# ESP32_AC_Controller.net
KiCad netlist of a schematic drawn in Altium Designer
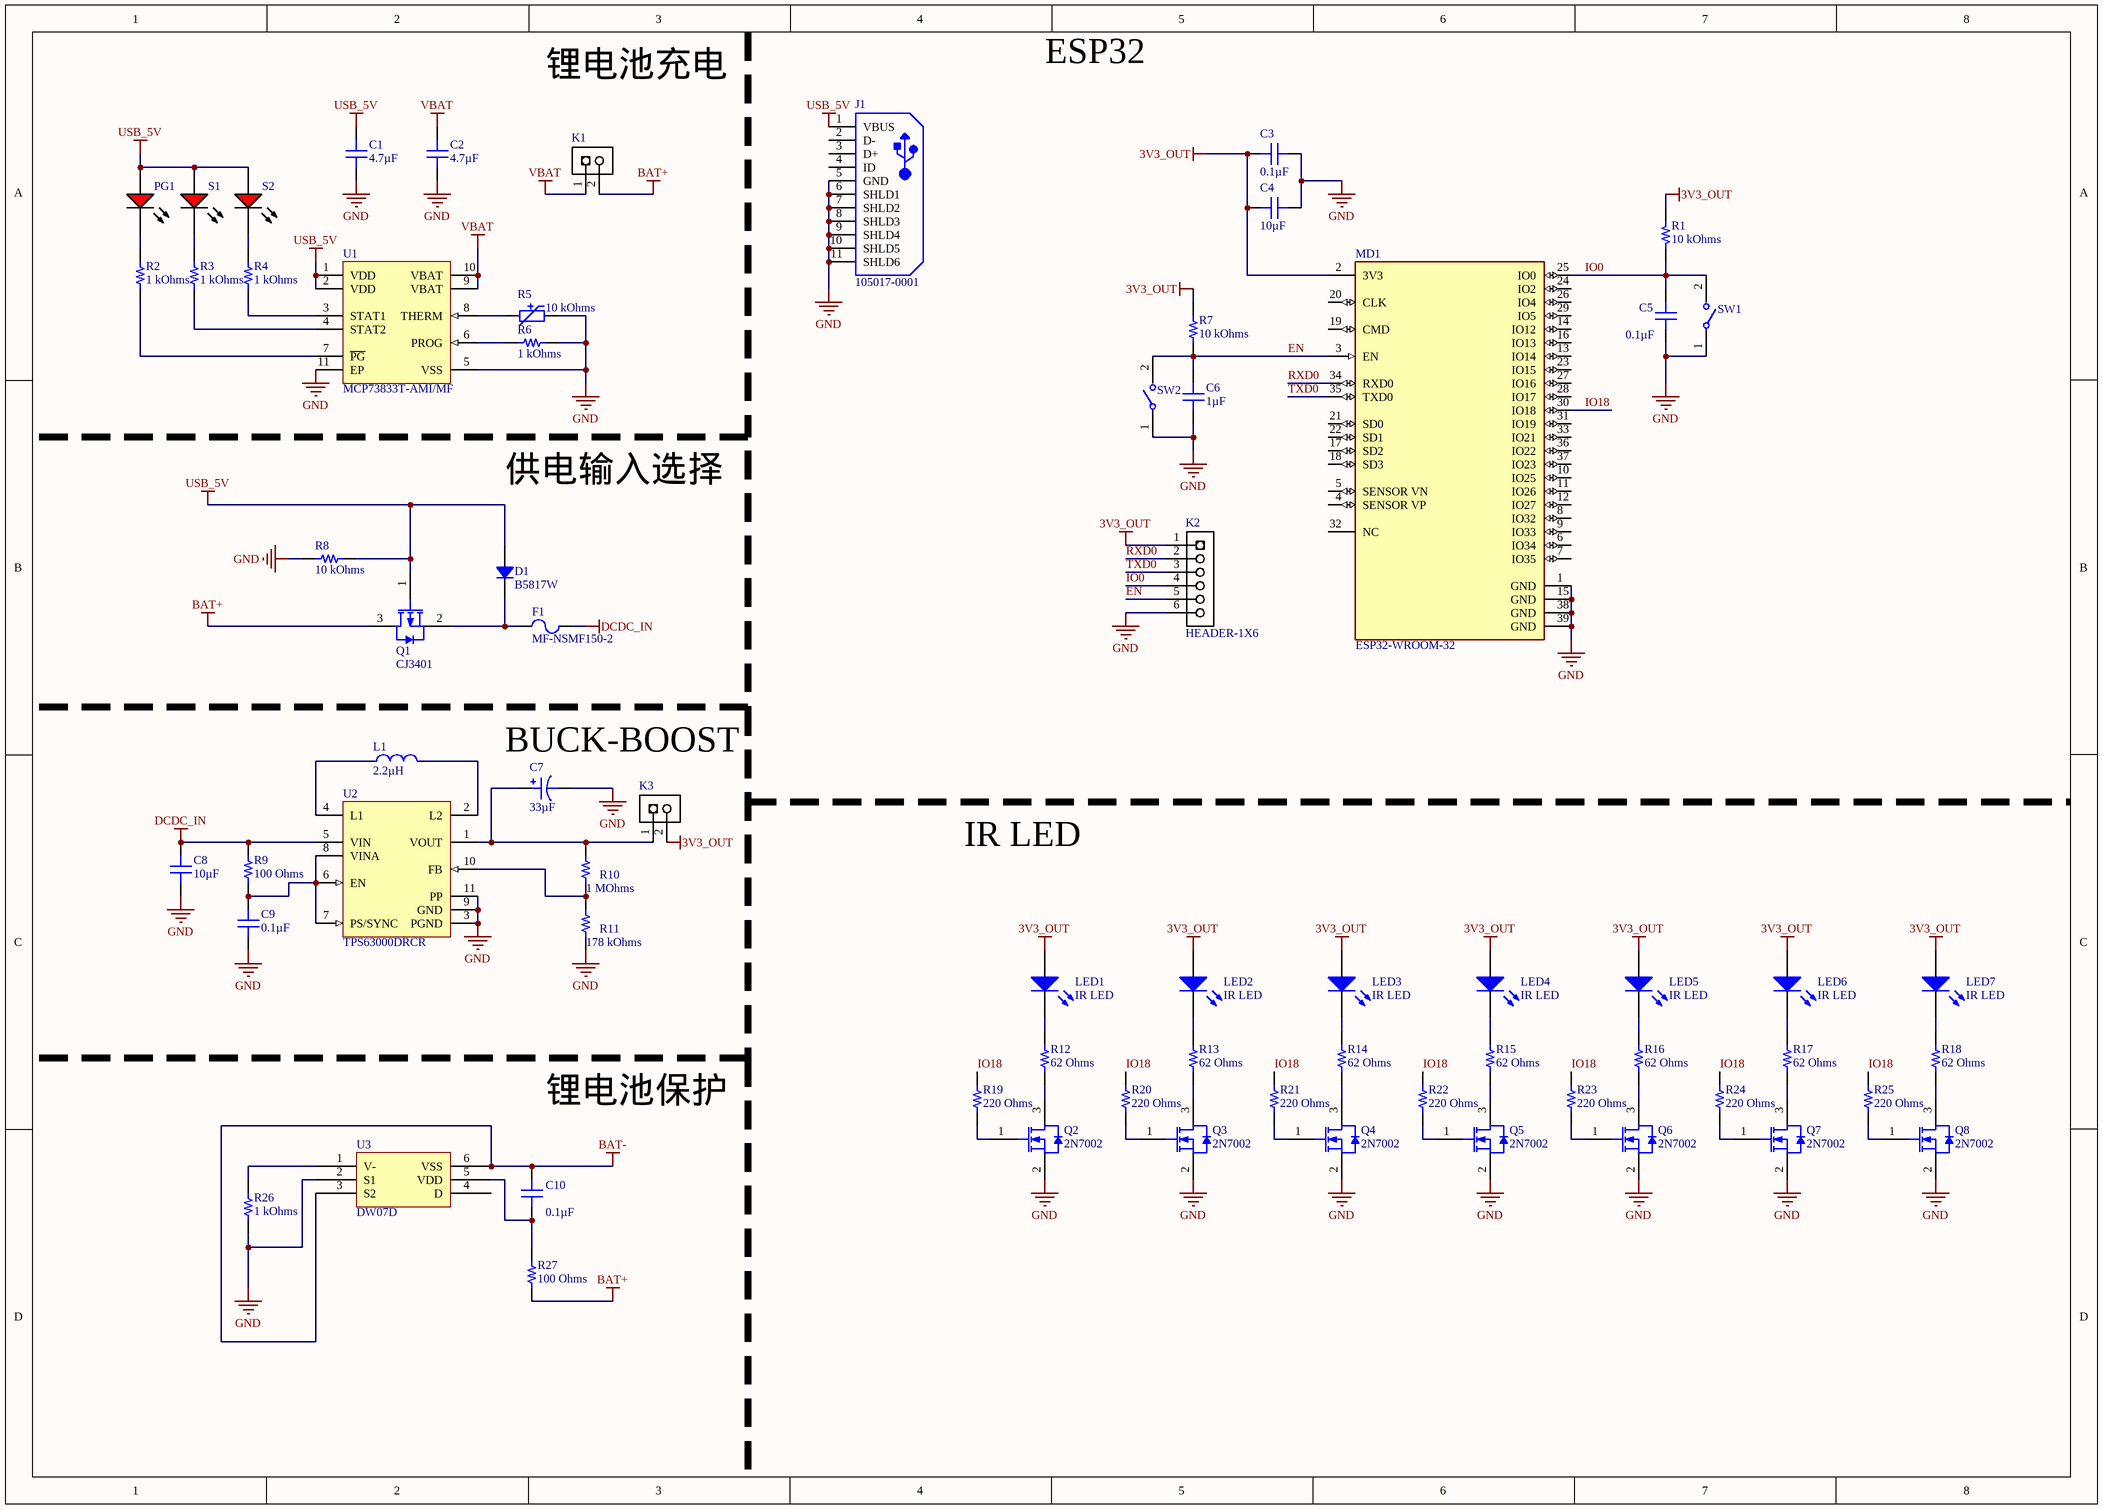
[diagram p0: ESP32_AC_Controller.SchDoc]

(export (version "E")
  (design (tool "Eeschema 10.0.6"))
  (components
    (comp (ref "C1")
      (value "4.7µF")
      (footprint "CAP 0603_1608")
      (description "CAP CER 0603 1UF 16V X7R 10%")
      (fields (field (name "PART NUMBER") "C0603C105K4RACAUTO") (field (name "MANUFACTURER") "KEMET"))
      (libsource (lib "Celestial Altium Library - altium_library") (part "Capacitor"))
    )
    (comp (ref "C2")
      (value "4.7µF")
      (footprint "CAP 0603_1608")
      (description "CAP CER 0603 1UF 16V X7R 10%")
      (fields (field (name "PART NUMBER") "C0603C105K4RACAUTO") (field (name "MANUFACTURER") "KEMET"))
      (libsource (lib "Celestial Altium Library - altium_library") (part "Capacitor"))
    )
    (comp (ref "C3")
      (value "0.1µF")
      (footprint "CAP 0603_1608")
      (description "CAP CER 0.1UF 10V X7R 0603")
      (fields (field (name "PART NUMBER") "C0603T104K8RAC7867") (field (name "MANUFACTURER") "KEMET"))
      (libsource (lib "Celestial Altium Library - altium_library") (part "Capacitor"))
    )
    (comp (ref "C4")
      (value "10µF")
      (footprint "CAP 0603_1608")
      (description "CAP CER 10UF 10V X5R 0603")
      (fields
        (field (name "PART NUMBER") "GRM188R61A106MAALD")
        (field (name "MANUFACTURER") "Murata Electronics")
      )
      (libsource (lib "Celestial Altium Library - altium_library") (part "Capacitor"))
    )
    (comp (ref "C5")
      (value "0.1µF")
      (footprint "CAP 0603_1608")
      (description "CAP CER 0.1UF 10V X7R 0603")
      (fields (field (name "PART NUMBER") "C0603T104K8RAC7867") (field (name "MANUFACTURER") "KEMET"))
      (libsource (lib "Celestial Altium Library - altium_library") (part "Capacitor"))
    )
    (comp (ref "C6")
      (value "1µF")
      (footprint "CAP 0603_1608")
      (description "CAP CER 1UF 10V X7R 0603")
      (fields (field (name "PART NUMBER") "CC0603KRX7R6BB105") (field (name "MANUFACTURER") "Yageo"))
      (libsource (lib "Celestial Altium Library - altium_library") (part "Capacitor"))
    )
    (comp (ref "C7")
      (value "33µF")
      (footprint "CAP POL 1411_3528")
      (description "CAP TANT 1UF 10% 35V 1411")
      (fields (field (name "PART NUMBER") "CWR11MH105KB") (field (name "MANUFACTURER") "KEMET"))
      (libsource (lib "Celestial Altium Library - altium_library") (part "Polarised Capacitor"))
    )
    (comp (ref "C8")
      (value "10µF")
      (footprint "CAP 0603_1608")
      (description "CAP CER 10UF 6.3V X5R 0603")
      (fields
        (field (name "PART NUMBER") "GRM188R60J106ME47D")
        (field (name "MANUFACTURER") "Murata Electronics")
      )
      (libsource (lib "Celestial Altium Library - altium_library") (part "Capacitor"))
    )
    (comp (ref "C9")
      (value "0.1µF")
      (footprint "CAP 0603_1608")
      (description "CAP CER 10UF 6.3V X5R 0603")
      (fields
        (field (name "PART NUMBER") "GRM188R60J106ME47D")
        (field (name "MANUFACTURER") "Murata Electronics")
      )
      (libsource (lib "Celestial Altium Library - altium_library") (part "Capacitor"))
    )
    (comp (ref "C10")
      (value "0.1µF")
      (footprint "CAP 0603_1608")
      (description "CAP CER 0.1UF 10V X7R 0603")
      (fields (field (name "PART NUMBER") "C0603T104K8RAC7867") (field (name "MANUFACTURER") "KEMET"))
      (libsource (lib "Celestial Altium Library - altium_library") (part "Capacitor"))
    )
    (comp (ref "D1")
      (value "B5817W")
      (footprint "SOD-123")
      (description "DIODE SCHOTTKY 30V 1A SOD-123")
      (fields (field (name "PART NUMBER") "B5818W-TP") (field (name "MANUFACTURER") "Micro Commercial Co"))
      (libsource (lib "Celestial Altium Library - altium_library") (part "Diode"))
    )
    (comp (ref "F1")
      (value "MF-NSMF150-2")
      (footprint "BOUR-MF-NSMF150-2_V")
      (description "PTC Resettable Fuse, 6 V, 100 A, -40 to 85 degC, 2-Pin SMD, RoHS, Tape and Reel")
      (fields (field (name "MANUFACTURER") "Bourns"))
      (libsource (lib "Altium Content Vault") (part "FUSE-2"))
    )
    (comp (ref "J1")
      (value "105017-0001")
      (footprint "USB-MICRO-B_V")
      (fields (field (name "MANUFACTURER") "Molex"))
      (libsource (lib "Altium Content Vault") (part "USB-5-6SHLD"))
    )
    (comp (ref "K1")
      (value "HEADER-1X2")
      (footprint "HEADER-1X2")
      (libsource (lib "vh_altium_library") (part "HEADER-1X2"))
    )
    (comp (ref "K2")
      (value "HEADER-1X6")
      (footprint "HEADER-1X6")
      (libsource (lib "vh_altium_library") (part "HEADER-1X6"))
    )
    (comp (ref "K3")
      (value "HEADER-1X2")
      (footprint "HEADER-1X2")
      (libsource (lib "vh_altium_library") (part "HEADER-1X2"))
    )
    (comp (ref "L1")
      (value "2.2µH")
      (footprint "FP-IHLP-2525CZ-FP_2_413x3-MFG")
      (description "Commercial Inductors, High Saturation Series 6.8uH 4.5A 60mΩ 20%")
      (fields (field (name "TOLERANCE") "20%"))
      (libsource (lib "Altium Content Vault") (part "725321dda6339637d4d059423bc1c3c"))
    )
    (comp (ref "LED1")
      (value "IR LED")
      (footprint "Type 5mm")
      (description "THT LED round mono-color waterclear, WL-TMRW ,Blue")
      (fields (field (name "MANUFACTURER") "Wuerth Elektronik") (field (name "PARTNUMBER") "151053BS04500"))
      (libsource (lib "Altium Content Vault") (part "WE-LED_K1A2-2"))
    )
    (comp (ref "LED2")
      (value "IR LED")
      (footprint "Type 5mm")
      (description "THT LED round mono-color waterclear, WL-TMRW ,Blue")
      (fields (field (name "MANUFACTURER") "Wuerth Elektronik") (field (name "PARTNUMBER") "151053BS04500"))
      (libsource (lib "Altium Content Vault") (part "WE-LED_K1A2-2"))
    )
    (comp (ref "LED3")
      (value "IR LED")
      (footprint "Type 5mm")
      (description "THT LED round mono-color waterclear, WL-TMRW ,Blue")
      (fields (field (name "MANUFACTURER") "Wuerth Elektronik") (field (name "PARTNUMBER") "151053BS04500"))
      (libsource (lib "Altium Content Vault") (part "WE-LED_K1A2-2"))
    )
    (comp (ref "LED4")
      (value "IR LED")
      (footprint "Type 5mm")
      (description "THT LED round mono-color waterclear, WL-TMRW ,Blue")
      (fields (field (name "MANUFACTURER") "Wuerth Elektronik") (field (name "PARTNUMBER") "151053BS04500"))
      (libsource (lib "Altium Content Vault") (part "WE-LED_K1A2-2"))
    )
    (comp (ref "LED5")
      (value "IR LED")
      (footprint "Type 5mm")
      (description "THT LED round mono-color waterclear, WL-TMRW ,Blue")
      (fields (field (name "MANUFACTURER") "Wuerth Elektronik") (field (name "PARTNUMBER") "151053BS04500"))
      (libsource (lib "Altium Content Vault") (part "WE-LED_K1A2-2"))
    )
    (comp (ref "LED6")
      (value "IR LED")
      (footprint "Type 5mm")
      (description "THT LED round mono-color waterclear, WL-TMRW ,Blue")
      (fields (field (name "MANUFACTURER") "Wuerth Elektronik") (field (name "PARTNUMBER") "151053BS04500"))
      (libsource (lib "Altium Content Vault") (part "WE-LED_K1A2-2"))
    )
    (comp (ref "LED7")
      (value "IR LED")
      (footprint "Type 5mm")
      (description "THT LED round mono-color waterclear, WL-TMRW ,Blue")
      (fields (field (name "MANUFACTURER") "Wuerth Elektronik") (field (name "PARTNUMBER") "151053BS04500"))
      (libsource (lib "Altium Content Vault") (part "WE-LED_K1A2-2"))
    )
    (comp (ref "MD1")
      (value "ESP32-WROOM-32")
      (footprint "FP-ESP32-WROOM-32-MFG")
      (description "RX TXRX MOD WIFI SURFACE MOUNT")
      (libsource (lib "Altium Content Vault") (part "ee866abf0b6c51247b7f5cdebf2f250"))
    )
    (comp (ref "PG1")
      (value "TLMS1100-GS08")
      (footprint "VISH-TLMX1100_V")
      (description "LED, RED, 2.1 V, -40 to 100 degC, 2-Pin SMD (0603), RoHS, Tape and Reel")
      (fields (field (name "TOLERANCE") "5%"))
      (libsource (lib "Altium Content Vault") (part "LED-RED-AK-2"))
    )
    (comp (ref "Q1")
      (value "CJ3401")
      (footprint "FAIR-SSOT3L-3_V")
      (fields (field (name "MANUFACTURER") "Fairchild Semiconductor"))
      (libsource (lib "Altium Content Vault") (part "PEMOS-GSD-3"))
    )
    (comp (ref "Q2")
      (value "2N7002")
      (footprint "STM-SOT-23-3_V")
      (description "N-channel 60 V, 1.8 Ohm, 0.35 A STripFET(TM) II Power MOSFET, SOT23")
      (fields (field (name "MANUFACTURER") "STMicroelectronics"))
      (libsource (lib "Altium Content Vault") (part "STM-NEMOS-G1S2D3-3"))
    )
    (comp (ref "Q3")
      (value "2N7002")
      (footprint "STM-SOT-23-3_V")
      (description "N-channel 60 V, 1.8 Ohm, 0.35 A STripFET(TM) II Power MOSFET, SOT23")
      (fields (field (name "MANUFACTURER") "STMicroelectronics"))
      (libsource (lib "Altium Content Vault") (part "STM-NEMOS-G1S2D3-3"))
    )
    (comp (ref "Q4")
      (value "2N7002")
      (footprint "STM-SOT-23-3_V")
      (description "N-channel 60 V, 1.8 Ohm, 0.35 A STripFET(TM) II Power MOSFET, SOT23")
      (fields (field (name "MANUFACTURER") "STMicroelectronics"))
      (libsource (lib "Altium Content Vault") (part "STM-NEMOS-G1S2D3-3"))
    )
    (comp (ref "Q5")
      (value "2N7002")
      (footprint "STM-SOT-23-3_V")
      (description "N-channel 60 V, 1.8 Ohm, 0.35 A STripFET(TM) II Power MOSFET, SOT23")
      (fields (field (name "MANUFACTURER") "STMicroelectronics"))
      (libsource (lib "Altium Content Vault") (part "STM-NEMOS-G1S2D3-3"))
    )
    (comp (ref "Q6")
      (value "2N7002")
      (footprint "STM-SOT-23-3_V")
      (description "N-channel 60 V, 1.8 Ohm, 0.35 A STripFET(TM) II Power MOSFET, SOT23")
      (fields (field (name "MANUFACTURER") "STMicroelectronics"))
      (libsource (lib "Altium Content Vault") (part "STM-NEMOS-G1S2D3-3"))
    )
    (comp (ref "Q7")
      (value "2N7002")
      (footprint "STM-SOT-23-3_V")
      (description "N-channel 60 V, 1.8 Ohm, 0.35 A STripFET(TM) II Power MOSFET, SOT23")
      (fields (field (name "MANUFACTURER") "STMicroelectronics"))
      (libsource (lib "Altium Content Vault") (part "STM-NEMOS-G1S2D3-3"))
    )
    (comp (ref "Q8")
      (value "2N7002")
      (footprint "STM-SOT-23-3_V")
      (description "N-channel 60 V, 1.8 Ohm, 0.35 A STripFET(TM) II Power MOSFET, SOT23")
      (fields (field (name "MANUFACTURER") "STMicroelectronics"))
      (libsource (lib "Altium Content Vault") (part "STM-NEMOS-G1S2D3-3"))
    )
    (comp (ref "R1")
      (value "10 kOhms")
      (footprint "RES 0603_1608")
      (description "RES 10K OHM 0.1% 1/16W 0603")
      (fields
        (field (name "PART NUMBER") "RNCS0603BKE10K0")
        (field (name "MANUFACTURER") "Stackpole Electronics Inc")
      )
      (libsource (lib "Celestial Altium Library - altium_library") (part "Resistor"))
    )
    (comp (ref "R2")
      (value "1 kOhms")
      (footprint "RES 0603_1608")
      (description "RES 10K OHM 0.1% 1/16W 0603")
      (fields
        (field (name "PART NUMBER") "RNCS0603BKE10K0")
        (field (name "MANUFACTURER") "Stackpole Electronics Inc")
      )
      (libsource (lib "Celestial Altium Library - altium_library") (part "Resistor"))
    )
    (comp (ref "R3")
      (value "1 kOhms")
      (footprint "RES 0603_1608")
      (description "RES 10K OHM 0.1% 1/16W 0603")
      (fields
        (field (name "PART NUMBER") "RNCS0603BKE10K0")
        (field (name "MANUFACTURER") "Stackpole Electronics Inc")
      )
      (libsource (lib "Celestial Altium Library - altium_library") (part "Resistor"))
    )
    (comp (ref "R4")
      (value "1 kOhms")
      (footprint "RES 0603_1608")
      (description "RES 10K OHM 0.1% 1/16W 0603")
      (fields
        (field (name "PART NUMBER") "RNCS0603BKE10K0")
        (field (name "MANUFACTURER") "Stackpole Electronics Inc")
      )
      (libsource (lib "Celestial Altium Library - altium_library") (part "Resistor"))
    )
    (comp (ref "R5")
      (value "10 kOhms")
      (footprint "PTC 0603_1608")
      (description "THERMISTOR PTC 470 OHM 50% 0603")
      (fields
        (field (name "PART NUMBER") "B59641A0145A062")
        (field (name "MANUFACTURER") "TDK Electronics Inc.")
      )
      (libsource (lib "Celestial Altium Library - altium_library") (part "Thermistor PTC"))
    )
    (comp (ref "R6")
      (value "1 kOhms")
      (footprint "RES 0603_1608")
      (description "RES 10K OHM 0.1% 1/16W 0603")
      (fields
        (field (name "PART NUMBER") "RNCS0603BKE10K0")
        (field (name "MANUFACTURER") "Stackpole Electronics Inc")
      )
      (libsource (lib "Celestial Altium Library - altium_library") (part "Resistor"))
    )
    (comp (ref "R7")
      (value "10 kOhms")
      (footprint "RES 0603_1608")
      (description "RES 10K OHM 0.1% 1/16W 0603")
      (fields
        (field (name "PART NUMBER") "RNCS0603BKE10K0")
        (field (name "MANUFACTURER") "Stackpole Electronics Inc")
      )
      (libsource (lib "Celestial Altium Library - altium_library") (part "Resistor"))
    )
    (comp (ref "R8")
      (value "10 kOhms")
      (footprint "RES 0603_1608")
      (description "RES 10K OHM 0.1% 1/16W 0603")
      (fields
        (field (name "PART NUMBER") "RNCS0603BKE10K0")
        (field (name "MANUFACTURER") "Stackpole Electronics Inc")
      )
      (libsource (lib "Celestial Altium Library - altium_library") (part "Resistor"))
    )
    (comp (ref "R9")
      (value "100 Ohms")
      (footprint "RES 0603_1608")
      (description "RES 10K OHM 0.1% 1/16W 0603")
      (fields
        (field (name "PART NUMBER") "RNCS0603BKE10K0")
        (field (name "MANUFACTURER") "Stackpole Electronics Inc")
      )
      (libsource (lib "Celestial Altium Library - altium_library") (part "Resistor"))
    )
    (comp (ref "R10")
      (value "1 MOhms")
      (footprint "RES 0603_1608")
      (description "RES 10K OHM 0.1% 1/16W 0603")
      (fields
        (field (name "PART NUMBER") "RNCS0603BKE10K0")
        (field (name "MANUFACTURER") "Stackpole Electronics Inc")
      )
      (libsource (lib "Celestial Altium Library - altium_library") (part "Resistor"))
    )
    (comp (ref "R11")
      (value "178 kOhms")
      (footprint "RES 0603_1608")
      (description "RES 10K OHM 0.1% 1/16W 0603")
      (fields
        (field (name "PART NUMBER") "RNCS0603BKE10K0")
        (field (name "MANUFACTURER") "Stackpole Electronics Inc")
      )
      (libsource (lib "Celestial Altium Library - altium_library") (part "Resistor"))
    )
    (comp (ref "R12")
      (value "62 Ohms")
      (footprint "RES 0603_1608")
      (description "RES SMD 62 OHM 1% 0.3W 0603")
      (fields (field (name "PART NUMBER") "SDR03EZPF62R0") (field (name "MANUFACTURER") "Rohm Semiconductor"))
      (libsource (lib "Celestial Altium Library - altium_library") (part "Resistor"))
    )
    (comp (ref "R13")
      (value "62 Ohms")
      (footprint "RES 0603_1608")
      (description "RES SMD 62 OHM 1% 0.3W 0603")
      (fields (field (name "PART NUMBER") "SDR03EZPF62R0") (field (name "MANUFACTURER") "Rohm Semiconductor"))
      (libsource (lib "Celestial Altium Library - altium_library") (part "Resistor"))
    )
    (comp (ref "R14")
      (value "62 Ohms")
      (footprint "RES 0603_1608")
      (description "RES SMD 62 OHM 1% 0.3W 0603")
      (fields (field (name "PART NUMBER") "SDR03EZPF62R0") (field (name "MANUFACTURER") "Rohm Semiconductor"))
      (libsource (lib "Celestial Altium Library - altium_library") (part "Resistor"))
    )
    (comp (ref "R15")
      (value "62 Ohms")
      (footprint "RES 0603_1608")
      (description "RES SMD 62 OHM 1% 0.3W 0603")
      (fields (field (name "PART NUMBER") "SDR03EZPF62R0") (field (name "MANUFACTURER") "Rohm Semiconductor"))
      (libsource (lib "Celestial Altium Library - altium_library") (part "Resistor"))
    )
    (comp (ref "R16")
      (value "62 Ohms")
      (footprint "RES 0603_1608")
      (description "RES SMD 62 OHM 1% 0.3W 0603")
      (fields (field (name "PART NUMBER") "SDR03EZPF62R0") (field (name "MANUFACTURER") "Rohm Semiconductor"))
      (libsource (lib "Celestial Altium Library - altium_library") (part "Resistor"))
    )
    (comp (ref "R17")
      (value "62 Ohms")
      (footprint "RES 0603_1608")
      (description "RES SMD 62 OHM 1% 0.3W 0603")
      (fields (field (name "PART NUMBER") "SDR03EZPF62R0") (field (name "MANUFACTURER") "Rohm Semiconductor"))
      (libsource (lib "Celestial Altium Library - altium_library") (part "Resistor"))
    )
    (comp (ref "R18")
      (value "62 Ohms")
      (footprint "RES 0603_1608")
      (description "RES SMD 62 OHM 1% 0.3W 0603")
      (fields (field (name "PART NUMBER") "SDR03EZPF62R0") (field (name "MANUFACTURER") "Rohm Semiconductor"))
      (libsource (lib "Celestial Altium Library - altium_library") (part "Resistor"))
    )
    (comp (ref "R19")
      (value "220 Ohms")
      (footprint "RES 0603_1608")
      (description "RES SMD 220 OHM 0.1% 1/16W 0603")
      (fields
        (field (name "PART NUMBER") "CPF0603B220RE1")
        (field (name "MANUFACTURER") "TE Connectivity Passive Product")
      )
      (libsource (lib "Celestial Altium Library - altium_library") (part "Resistor"))
    )
    (comp (ref "R20")
      (value "220 Ohms")
      (footprint "RES 0603_1608")
      (description "RES SMD 220 OHM 0.1% 1/16W 0603")
      (fields
        (field (name "PART NUMBER") "CPF0603B220RE1")
        (field (name "MANUFACTURER") "TE Connectivity Passive Product")
      )
      (libsource (lib "Celestial Altium Library - altium_library") (part "Resistor"))
    )
    (comp (ref "R21")
      (value "220 Ohms")
      (footprint "RES 0603_1608")
      (description "RES SMD 220 OHM 0.1% 1/16W 0603")
      (fields
        (field (name "PART NUMBER") "CPF0603B220RE1")
        (field (name "MANUFACTURER") "TE Connectivity Passive Product")
      )
      (libsource (lib "Celestial Altium Library - altium_library") (part "Resistor"))
    )
    (comp (ref "R22")
      (value "220 Ohms")
      (footprint "RES 0603_1608")
      (description "RES SMD 220 OHM 0.1% 1/16W 0603")
      (fields
        (field (name "PART NUMBER") "CPF0603B220RE1")
        (field (name "MANUFACTURER") "TE Connectivity Passive Product")
      )
      (libsource (lib "Celestial Altium Library - altium_library") (part "Resistor"))
    )
    (comp (ref "R23")
      (value "220 Ohms")
      (footprint "RES 0603_1608")
      (description "RES SMD 220 OHM 0.1% 1/16W 0603")
      (fields
        (field (name "PART NUMBER") "CPF0603B220RE1")
        (field (name "MANUFACTURER") "TE Connectivity Passive Product")
      )
      (libsource (lib "Celestial Altium Library - altium_library") (part "Resistor"))
    )
    (comp (ref "R24")
      (value "220 Ohms")
      (footprint "RES 0603_1608")
      (description "RES SMD 220 OHM 0.1% 1/16W 0603")
      (fields
        (field (name "PART NUMBER") "CPF0603B220RE1")
        (field (name "MANUFACTURER") "TE Connectivity Passive Product")
      )
      (libsource (lib "Celestial Altium Library - altium_library") (part "Resistor"))
    )
    (comp (ref "R25")
      (value "220 Ohms")
      (footprint "RES 0603_1608")
      (description "RES SMD 220 OHM 0.1% 1/16W 0603")
      (fields
        (field (name "PART NUMBER") "CPF0603B220RE1")
        (field (name "MANUFACTURER") "TE Connectivity Passive Product")
      )
      (libsource (lib "Celestial Altium Library - altium_library") (part "Resistor"))
    )
    (comp (ref "R26")
      (value "1 kOhms")
      (footprint "RES 0603_1608")
      (description "RES SMD 1K OHM 1% 1/10W 0603")
      (fields (field (name "PART NUMBER") "AC0603FR-071KL") (field (name "MANUFACTURER") "Yageo"))
      (libsource (lib "Celestial Altium Library - altium_library") (part "Resistor"))
    )
    (comp (ref "R27")
      (value "100 Ohms")
      (footprint "RES 0603_1608")
      (description "RES SMD 100 OHM 1% 1/10W 0603")
      (fields (field (name "PART NUMBER") "AC0603FR-07100RL") (field (name "MANUFACTURER") "Yageo"))
      (libsource (lib "Celestial Altium Library - altium_library") (part "Resistor"))
    )
    (comp (ref "S1")
      (value "TLMS1100-GS08")
      (footprint "VISH-TLMX1100_V")
      (description "LED, RED, 2.1 V, -40 to 100 degC, 2-Pin SMD (0603), RoHS, Tape and Reel")
      (fields (field (name "TOLERANCE") "5%"))
      (libsource (lib "Altium Content Vault") (part "LED-RED-AK-2"))
    )
    (comp (ref "S2")
      (value "TLMS1100-GS08")
      (footprint "VISH-TLMX1100_V")
      (description "LED, RED, 2.1 V, -40 to 100 degC, 2-Pin SMD (0603), RoHS, Tape and Reel")
      (fields (field (name "TOLERANCE") "5%"))
      (libsource (lib "Altium Content Vault") (part "LED-RED-AK-2"))
    )
    (comp (ref "SW1")
      (value "B3U-1000P")
      (footprint "FP-B3U-1000P-MFG")
      (description "SWITCH TACTILE SPST-NO 0.05A 12V")
      (libsource (lib "Altium Content Vault") (part "ae622034201233ca1abcedc05908f33"))
    )
    (comp (ref "SW2")
      (value "B3U-1000P")
      (footprint "FP-B3U-1000P-MFG")
      (description "SWITCH TACTILE SPST-NO 0.05A 12V")
      (libsource (lib "Altium Content Vault") (part "ae622034201233ca1abcedc05908f33"))
    )
    (comp (ref "U1")
      (value "MCP73833T-AMI/MF")
      (footprint "DFN-MF10")
      (libsource (lib "Altium Content Vault") (part "PM-BM-MCP73833-IL11"))
    )
    (comp (ref "U2")
      (value "TPS63000DRCR")
      (footprint "DRC0010J_V")
      (fields (field (name "MANUFACTURER") "Texas Instruments"))
      (libsource (lib "Altium Content Vault") (part "TI-TPS63000DRC10-3000X1650TP"))
    )
    (comp (ref "U3")
      (value "DW07D")
      (footprint "DW07D")
      (description "锂电池保护IC")
      (libsource (lib "MyIntegrated_Library") (part "DW07D"))
    )
  )
  (nets
    (net (code "1") (name "/EN") (class "Default")
      (node (ref "C6") (pin "2") (pinfunction "2_2") (pintype "passive"))
      (node (ref "K2") (pin "5") (pintype "passive"))
      (node (ref "MD1") (pin "3") (pinfunction "EN_3") (pintype "input"))
      (node (ref "R7") (pin "1") (pinfunction "1_1") (pintype "passive"))
      (node (ref "SW2") (pin "2") (pinfunction "2_2") (pintype "passive"))
    )
    (net (code "2") (name "/IO0") (class "Default")
      (node (ref "C5") (pin "1") (pinfunction "1_1") (pintype "passive"))
      (node (ref "K2") (pin "4") (pintype "passive"))
      (node (ref "MD1") (pin "25") (pinfunction "IO0_25") (pintype "bidirectional"))
      (node (ref "R1") (pin "1") (pinfunction "1_1") (pintype "passive"))
      (node (ref "SW1") (pin "2") (pinfunction "2_2") (pintype "passive"))
    )
    (net (code "3") (name "/IO18") (class "Default")
      (node (ref "MD1") (pin "30") (pinfunction "IO18_30") (pintype "bidirectional"))
      (node (ref "R19") (pin "2") (pinfunction "2_2") (pintype "passive"))
      (node (ref "R20") (pin "2") (pinfunction "2_2") (pintype "passive"))
      (node (ref "R21") (pin "2") (pinfunction "2_2") (pintype "passive"))
      (node (ref "R22") (pin "2") (pinfunction "2_2") (pintype "passive"))
      (node (ref "R23") (pin "2") (pinfunction "2_2") (pintype "passive"))
      (node (ref "R24") (pin "2") (pinfunction "2_2") (pintype "passive"))
      (node (ref "R25") (pin "2") (pinfunction "2_2") (pintype "passive"))
    )
    (net (code "4") (name "/RXD0") (class "Default")
      (node (ref "K2") (pin "2") (pintype "passive"))
      (node (ref "MD1") (pin "34") (pinfunction "RXD0_34") (pintype "bidirectional"))
    )
    (net (code "5") (name "/TXD0") (class "Default")
      (node (ref "K2") (pin "3") (pintype "passive"))
      (node (ref "MD1") (pin "35") (pinfunction "TXD0_35") (pintype "bidirectional"))
    )
    (net (code "6") (name "3V3_OUT") (class "Default")
      (node (ref "C3") (pin "2") (pinfunction "2_2") (pintype "passive"))
      (node (ref "C4") (pin "1") (pinfunction "1_1") (pintype "passive"))
      (node (ref "K2") (pin "1") (pintype "passive"))
      (node (ref "K3") (pin "2") (pintype "passive"))
      (node (ref "LED1") (pin "2") (pinfunction "A_2") (pintype "passive"))
      (node (ref "LED2") (pin "2") (pinfunction "A_2") (pintype "passive"))
      (node (ref "LED3") (pin "2") (pinfunction "A_2") (pintype "passive"))
      (node (ref "LED4") (pin "2") (pinfunction "A_2") (pintype "passive"))
      (node (ref "LED5") (pin "2") (pinfunction "A_2") (pintype "passive"))
      (node (ref "LED6") (pin "2") (pinfunction "A_2") (pintype "passive"))
      (node (ref "LED7") (pin "2") (pinfunction "A_2") (pintype "passive"))
      (node (ref "MD1") (pin "2") (pinfunction "3V3_2") (pintype "power_in"))
      (node (ref "R1") (pin "2") (pinfunction "2_2") (pintype "passive"))
      (node (ref "R7") (pin "2") (pinfunction "2_2") (pintype "passive"))
    )
    (net (code "7") (name "BAT+") (class "Default")
      (node (ref "K1") (pin "2") (pintype "passive"))
      (node (ref "Q1") (pin "3") (pinfunction "DRAIN_3") (pintype "passive"))
      (node (ref "R27") (pin "1") (pinfunction "1_1") (pintype "passive"))
    )
    (net (code "8") (name "BAT-") (class "Default")
      (node (ref "C10") (pin "1") (pinfunction "1_1") (pintype "passive"))
      (node (ref "U3") (pin "3") (pinfunction "S2_3") (pintype "passive"))
      (node (ref "U3") (pin "6") (pinfunction "VSS_6") (pintype "passive"))
    )
    (net (code "9") (name "DCDC_IN") (class "Default")
      (node (ref "C8") (pin "2") (pinfunction "2_2") (pintype "passive"))
      (node (ref "F1") (pin "2") (pinfunction "2_2") (pintype "passive"))
      (node (ref "R9") (pin "1") (pinfunction "1_1") (pintype "passive"))
      (node (ref "U2") (pin "5") (pinfunction "VIN_5") (pintype "power_in"))
    )
    (net (code "10") (name "GND") (class "Default")
      (node (ref "C1") (pin "1") (pinfunction "1_1") (pintype "passive"))
      (node (ref "C2") (pin "1") (pinfunction "1_1") (pintype "passive"))
      (node (ref "C3") (pin "1") (pinfunction "1_1") (pintype "passive"))
      (node (ref "C4") (pin "2") (pinfunction "2_2") (pintype "passive"))
      (node (ref "C5") (pin "2") (pinfunction "2_2") (pintype "passive"))
      (node (ref "C6") (pin "1") (pinfunction "1_1") (pintype "passive"))
      (node (ref "C7") (pin "2") (pinfunction "2_2") (pintype "passive"))
      (node (ref "C8") (pin "1") (pinfunction "1_1") (pintype "passive"))
      (node (ref "C9") (pin "2") (pinfunction "2_2") (pintype "passive"))
      (node (ref "J1") (pin "10") (pinfunction "SHLD5_10") (pintype "passive"))
      (node (ref "J1") (pin "11") (pinfunction "SHLD6_11") (pintype "passive"))
      (node (ref "J1") (pin "5") (pinfunction "GND_5") (pintype "passive"))
      (node (ref "J1") (pin "6") (pinfunction "SHLD1_6") (pintype "passive"))
      (node (ref "J1") (pin "7") (pinfunction "SHLD2_7") (pintype "passive"))
      (node (ref "J1") (pin "8") (pinfunction "SHLD3_8") (pintype "passive"))
      (node (ref "J1") (pin "9") (pinfunction "SHLD4_9") (pintype "passive"))
      (node (ref "K2") (pin "6") (pintype "passive"))
      (node (ref "MD1") (pin "1") (pinfunction "GND_1") (pintype "power_in"))
      (node (ref "MD1") (pin "15") (pinfunction "GND_15") (pintype "power_in"))
      (node (ref "MD1") (pin "38") (pinfunction "GND_38") (pintype "power_in"))
      (node (ref "MD1") (pin "39") (pinfunction "GND_39") (pintype "power_in"))
      (node (ref "Q2") (pin "2") (pinfunction "S_2") (pintype "passive"))
      (node (ref "Q3") (pin "2") (pinfunction "S_2") (pintype "passive"))
      (node (ref "Q4") (pin "2") (pinfunction "S_2") (pintype "passive"))
      (node (ref "Q5") (pin "2") (pinfunction "S_2") (pintype "passive"))
      (node (ref "Q6") (pin "2") (pinfunction "S_2") (pintype "passive"))
      (node (ref "Q7") (pin "2") (pinfunction "S_2") (pintype "passive"))
      (node (ref "Q8") (pin "2") (pinfunction "S_2") (pintype "passive"))
      (node (ref "R11") (pin "2") (pinfunction "2_2") (pintype "passive"))
      (node (ref "R26") (pin "1") (pinfunction "1_1") (pintype "passive"))
      (node (ref "R5") (pin "1") (pinfunction "1_1") (pintype "passive"))
      (node (ref "R6") (pin "1") (pinfunction "1_1") (pintype "passive"))
      (node (ref "R8") (pin "2") (pinfunction "2_2") (pintype "passive"))
      (node (ref "SW1") (pin "1") (pinfunction "1_1") (pintype "passive"))
      (node (ref "SW2") (pin "1") (pinfunction "1_1") (pintype "passive"))
      (node (ref "U1") (pin "11") (pinfunction "EP_11") (pintype "power_in"))
      (node (ref "U1") (pin "5") (pinfunction "VSS_5") (pintype "power_in"))
      (node (ref "U2") (pin "11") (pinfunction "PP_11") (pintype "power_in"))
      (node (ref "U2") (pin "3") (pinfunction "PGND_3") (pintype "power_in"))
      (node (ref "U2") (pin "9") (pinfunction "GND_9") (pintype "power_in"))
      (node (ref "U3") (pin "2") (pinfunction "S1_2") (pintype "passive"))
    )
    (net (code "11") (name "Net-(LED1-K)") (class "Default")
      (node (ref "LED1") (pin "1") (pinfunction "K_1") (pintype "passive"))
      (node (ref "R12") (pin "2") (pinfunction "2_2") (pintype "passive"))
    )
    (net (code "12") (name "Net-(LED2-K)") (class "Default")
      (node (ref "LED2") (pin "1") (pinfunction "K_1") (pintype "passive"))
      (node (ref "R13") (pin "2") (pinfunction "2_2") (pintype "passive"))
    )
    (net (code "13") (name "Net-(LED3-K)") (class "Default")
      (node (ref "LED3") (pin "1") (pinfunction "K_1") (pintype "passive"))
      (node (ref "R14") (pin "2") (pinfunction "2_2") (pintype "passive"))
    )
    (net (code "14") (name "Net-(LED4-K)") (class "Default")
      (node (ref "LED4") (pin "1") (pinfunction "K_1") (pintype "passive"))
      (node (ref "R15") (pin "2") (pinfunction "2_2") (pintype "passive"))
    )
    (net (code "15") (name "Net-(LED5-K)") (class "Default")
      (node (ref "LED5") (pin "1") (pinfunction "K_1") (pintype "passive"))
      (node (ref "R16") (pin "2") (pinfunction "2_2") (pintype "passive"))
    )
    (net (code "16") (name "Net-(LED6-K)") (class "Default")
      (node (ref "LED6") (pin "1") (pinfunction "K_1") (pintype "passive"))
      (node (ref "R17") (pin "2") (pinfunction "2_2") (pintype "passive"))
    )
    (net (code "17") (name "Net-(LED7-K)") (class "Default")
      (node (ref "LED7") (pin "1") (pinfunction "K_1") (pintype "passive"))
      (node (ref "R18") (pin "2") (pinfunction "2_2") (pintype "passive"))
    )
    (net (code "18") (name "Net-(PG1-K)") (class "Default")
      (node (ref "PG1") (pin "2") (pinfunction "K_2") (pintype "passive"))
      (node (ref "R2") (pin "2") (pinfunction "2_2") (pintype "passive"))
    )
    (net (code "19") (name "Net-(Q1-SOURCE)") (class "Default")
      (node (ref "D1") (pin "2") (pinfunction "2_2") (pintype "passive"))
      (node (ref "F1") (pin "1") (pinfunction "1_1") (pintype "passive"))
      (node (ref "Q1") (pin "2") (pinfunction "SOURCE_2") (pintype "passive"))
    )
    (net (code "20") (name "Net-(Q2-D)") (class "Default")
      (node (ref "Q2") (pin "3") (pinfunction "D_3") (pintype "passive"))
      (node (ref "R12") (pin "1") (pinfunction "1_1") (pintype "passive"))
    )
    (net (code "21") (name "Net-(Q2-G)") (class "Default")
      (node (ref "Q2") (pin "1") (pinfunction "G_1") (pintype "passive"))
      (node (ref "R19") (pin "1") (pinfunction "1_1") (pintype "passive"))
    )
    (net (code "22") (name "Net-(Q3-D)") (class "Default")
      (node (ref "Q3") (pin "3") (pinfunction "D_3") (pintype "passive"))
      (node (ref "R13") (pin "1") (pinfunction "1_1") (pintype "passive"))
    )
    (net (code "23") (name "Net-(Q3-G)") (class "Default")
      (node (ref "Q3") (pin "1") (pinfunction "G_1") (pintype "passive"))
      (node (ref "R20") (pin "1") (pinfunction "1_1") (pintype "passive"))
    )
    (net (code "24") (name "Net-(Q4-D)") (class "Default")
      (node (ref "Q4") (pin "3") (pinfunction "D_3") (pintype "passive"))
      (node (ref "R14") (pin "1") (pinfunction "1_1") (pintype "passive"))
    )
    (net (code "25") (name "Net-(Q4-G)") (class "Default")
      (node (ref "Q4") (pin "1") (pinfunction "G_1") (pintype "passive"))
      (node (ref "R21") (pin "1") (pinfunction "1_1") (pintype "passive"))
    )
    (net (code "26") (name "Net-(Q5-D)") (class "Default")
      (node (ref "Q5") (pin "3") (pinfunction "D_3") (pintype "passive"))
      (node (ref "R15") (pin "1") (pinfunction "1_1") (pintype "passive"))
    )
    (net (code "27") (name "Net-(Q5-G)") (class "Default")
      (node (ref "Q5") (pin "1") (pinfunction "G_1") (pintype "passive"))
      (node (ref "R22") (pin "1") (pinfunction "1_1") (pintype "passive"))
    )
    (net (code "28") (name "Net-(Q6-D)") (class "Default")
      (node (ref "Q6") (pin "3") (pinfunction "D_3") (pintype "passive"))
      (node (ref "R16") (pin "1") (pinfunction "1_1") (pintype "passive"))
    )
    (net (code "29") (name "Net-(Q6-G)") (class "Default")
      (node (ref "Q6") (pin "1") (pinfunction "G_1") (pintype "passive"))
      (node (ref "R23") (pin "1") (pinfunction "1_1") (pintype "passive"))
    )
    (net (code "30") (name "Net-(Q7-D)") (class "Default")
      (node (ref "Q7") (pin "3") (pinfunction "D_3") (pintype "passive"))
      (node (ref "R17") (pin "1") (pinfunction "1_1") (pintype "passive"))
    )
    (net (code "31") (name "Net-(Q7-G)") (class "Default")
      (node (ref "Q7") (pin "1") (pinfunction "G_1") (pintype "passive"))
      (node (ref "R24") (pin "1") (pinfunction "1_1") (pintype "passive"))
    )
    (net (code "32") (name "Net-(Q8-D)") (class "Default")
      (node (ref "Q8") (pin "3") (pinfunction "D_3") (pintype "passive"))
      (node (ref "R18") (pin "1") (pinfunction "1_1") (pintype "passive"))
    )
    (net (code "33") (name "Net-(Q8-G)") (class "Default")
      (node (ref "Q8") (pin "1") (pinfunction "G_1") (pintype "passive"))
      (node (ref "R25") (pin "1") (pinfunction "1_1") (pintype "passive"))
    )
    (net (code "34") (name "Net-(S1-K)") (class "Default")
      (node (ref "R3") (pin "2") (pinfunction "2_2") (pintype "passive"))
      (node (ref "S1") (pin "2") (pinfunction "K_2") (pintype "passive"))
    )
    (net (code "35") (name "Net-(S2-K)") (class "Default")
      (node (ref "R4") (pin "2") (pinfunction "2_2") (pintype "passive"))
      (node (ref "S2") (pin "2") (pinfunction "K_2") (pintype "passive"))
    )
    (net (code "36") (name "Net-(U1-PROG)") (class "Default")
      (node (ref "R6") (pin "2") (pinfunction "2_2") (pintype "passive"))
      (node (ref "U1") (pin "6") (pinfunction "PROG_6") (pintype "input"))
    )
    (net (code "37") (name "Net-(U1-STAT1)") (class "Default")
      (node (ref "R4") (pin "1") (pinfunction "1_1") (pintype "passive"))
      (node (ref "U1") (pin "3") (pinfunction "STAT1_3") (pintype "open_collector"))
    )
    (net (code "38") (name "Net-(U1-STAT2)") (class "Default")
      (node (ref "R3") (pin "1") (pinfunction "1_1") (pintype "passive"))
      (node (ref "U1") (pin "4") (pinfunction "STAT2_4") (pintype "open_collector"))
    )
    (net (code "39") (name "Net-(U1-THERM)") (class "Default")
      (node (ref "R5") (pin "2") (pinfunction "2_2") (pintype "passive"))
      (node (ref "U1") (pin "8") (pinfunction "THERM_8") (pintype "input"))
    )
    (net (code "40") (name "Net-(U1-~{PG})") (class "Default")
      (node (ref "R2") (pin "1") (pinfunction "1_1") (pintype "passive"))
      (node (ref "U1") (pin "7") (pinfunction "~{PG}_7") (pintype "open_collector"))
    )
    (net (code "41") (name "Net-(U2-EN)") (class "Default")
      (node (ref "C9") (pin "1") (pinfunction "1_1") (pintype "passive"))
      (node (ref "R9") (pin "2") (pinfunction "2_2") (pintype "passive"))
      (node (ref "U2") (pin "6") (pinfunction "EN_6") (pintype "input"))
      (node (ref "U2") (pin "7") (pinfunction "PS/SYNC_7") (pintype "input"))
      (node (ref "U2") (pin "8") (pinfunction "VINA_8") (pintype "power_in"))
    )
    (net (code "42") (name "Net-(U2-FB)") (class "Default")
      (node (ref "R10") (pin "2") (pinfunction "2_2") (pintype "passive"))
      (node (ref "R11") (pin "1") (pinfunction "1_1") (pintype "passive"))
      (node (ref "U2") (pin "10") (pinfunction "FB_10") (pintype "input"))
    )
    (net (code "43") (name "Net-(U2-L1)") (class "Default")
      (node (ref "L1") (pin "1") (pinfunction "1_1") (pintype "passive"))
      (node (ref "U2") (pin "4") (pinfunction "L1_4") (pintype "passive"))
    )
    (net (code "44") (name "Net-(U2-L2)") (class "Default")
      (node (ref "L1") (pin "2") (pinfunction "2_2") (pintype "passive"))
      (node (ref "U2") (pin "2") (pinfunction "L2_2") (pintype "passive"))
    )
    (net (code "45") (name "Net-(U2-VOUT)") (class "Default")
      (node (ref "C7") (pin "1") (pinfunction "1_1") (pintype "passive"))
      (node (ref "K3") (pin "1") (pintype "passive"))
      (node (ref "R10") (pin "1") (pinfunction "1_1") (pintype "passive"))
      (node (ref "U2") (pin "1") (pinfunction "VOUT_1") (pintype "power_in"))
    )
    (net (code "46") (name "Net-(U3-V-)") (class "Default")
      (node (ref "R26") (pin "2") (pinfunction "2_2") (pintype "passive"))
      (node (ref "U3") (pin "1") (pinfunction "V-_1") (pintype "passive"))
    )
    (net (code "47") (name "Net-(U3-VDD)") (class "Default")
      (node (ref "C10") (pin "2") (pinfunction "2_2") (pintype "passive"))
      (node (ref "R27") (pin "2") (pinfunction "2_2") (pintype "passive"))
      (node (ref "U3") (pin "5") (pinfunction "VDD_5") (pintype "passive"))
    )
    (net (code "48") (name "USB_5V") (class "Default")
      (node (ref "C1") (pin "2") (pinfunction "2_2") (pintype "passive"))
      (node (ref "D1") (pin "1") (pinfunction "1_1") (pintype "passive"))
      (node (ref "J1") (pin "1") (pinfunction "VBUS_1") (pintype "passive"))
      (node (ref "PG1") (pin "1") (pinfunction "A_1") (pintype "passive"))
      (node (ref "Q1") (pin "1") (pinfunction "GATE_1") (pintype "passive"))
      (node (ref "R8") (pin "1") (pinfunction "1_1") (pintype "passive"))
      (node (ref "S1") (pin "1") (pinfunction "A_1") (pintype "passive"))
      (node (ref "S2") (pin "1") (pinfunction "A_1") (pintype "passive"))
      (node (ref "U1") (pin "1") (pinfunction "VDD_1") (pintype "power_in"))
      (node (ref "U1") (pin "2") (pinfunction "VDD_2") (pintype "power_in"))
    )
    (net (code "49") (name "VBAT") (class "Default")
      (node (ref "C2") (pin "2") (pinfunction "2_2") (pintype "passive"))
      (node (ref "K1") (pin "1") (pintype "passive"))
      (node (ref "U1") (pin "10") (pinfunction "VBAT_10") (pintype "power_in"))
      (node (ref "U1") (pin "9") (pinfunction "VBAT_9") (pintype "power_in"))
    )
    (net (code "50") (name "unconnected-(J1-D+-Pad3)") (class "Default")
      (node (ref "J1") (pin "3") (pinfunction "D+_3") (pintype "passive"))
    )
    (net (code "51") (name "unconnected-(J1-D--Pad2)") (class "Default")
      (node (ref "J1") (pin "2") (pinfunction "D-_2") (pintype "passive"))
    )
    (net (code "52") (name "unconnected-(J1-ID-Pad4)") (class "Default")
      (node (ref "J1") (pin "4") (pinfunction "ID_4") (pintype "passive"))
    )
    (net (code "53") (name "unconnected-(MD1-CLK-Pad20)") (class "Default")
      (node (ref "MD1") (pin "20") (pinfunction "CLK_20") (pintype "bidirectional"))
    )
    (net (code "54") (name "unconnected-(MD1-CMD-Pad19)") (class "Default")
      (node (ref "MD1") (pin "19") (pinfunction "CMD_19") (pintype "bidirectional"))
    )
    (net (code "55") (name "unconnected-(MD1-IO2-Pad24)") (class "Default")
      (node (ref "MD1") (pin "24") (pinfunction "IO2_24") (pintype "bidirectional"))
    )
    (net (code "56") (name "unconnected-(MD1-IO4-Pad26)") (class "Default")
      (node (ref "MD1") (pin "26") (pinfunction "IO4_26") (pintype "bidirectional"))
    )
    (net (code "57") (name "unconnected-(MD1-IO5-Pad29)") (class "Default")
      (node (ref "MD1") (pin "29") (pinfunction "IO5_29") (pintype "bidirectional"))
    )
    (net (code "58") (name "unconnected-(MD1-IO12-Pad14)") (class "Default")
      (node (ref "MD1") (pin "14") (pinfunction "IO12_14") (pintype "bidirectional"))
    )
    (net (code "59") (name "unconnected-(MD1-IO13-Pad16)") (class "Default")
      (node (ref "MD1") (pin "16") (pinfunction "IO13_16") (pintype "bidirectional"))
    )
    (net (code "60") (name "unconnected-(MD1-IO14-Pad13)") (class "Default")
      (node (ref "MD1") (pin "13") (pinfunction "IO14_13") (pintype "bidirectional"))
    )
    (net (code "61") (name "unconnected-(MD1-IO15-Pad23)") (class "Default")
      (node (ref "MD1") (pin "23") (pinfunction "IO15_23") (pintype "bidirectional"))
    )
    (net (code "62") (name "unconnected-(MD1-IO16-Pad27)") (class "Default")
      (node (ref "MD1") (pin "27") (pinfunction "IO16_27") (pintype "bidirectional"))
    )
    (net (code "63") (name "unconnected-(MD1-IO17-Pad28)") (class "Default")
      (node (ref "MD1") (pin "28") (pinfunction "IO17_28") (pintype "bidirectional"))
    )
    (net (code "64") (name "unconnected-(MD1-IO19-Pad31)") (class "Default")
      (node (ref "MD1") (pin "31") (pinfunction "IO19_31") (pintype "bidirectional"))
    )
    (net (code "65") (name "unconnected-(MD1-IO21-Pad33)") (class "Default")
      (node (ref "MD1") (pin "33") (pinfunction "IO21_33") (pintype "bidirectional"))
    )
    (net (code "66") (name "unconnected-(MD1-IO22-Pad36)") (class "Default")
      (node (ref "MD1") (pin "36") (pinfunction "IO22_36") (pintype "bidirectional"))
    )
    (net (code "67") (name "unconnected-(MD1-IO23-Pad37)") (class "Default")
      (node (ref "MD1") (pin "37") (pinfunction "IO23_37") (pintype "bidirectional"))
    )
    (net (code "68") (name "unconnected-(MD1-IO25-Pad10)") (class "Default")
      (node (ref "MD1") (pin "10") (pinfunction "IO25_10") (pintype "bidirectional"))
    )
    (net (code "69") (name "unconnected-(MD1-IO26-Pad11)") (class "Default")
      (node (ref "MD1") (pin "11") (pinfunction "IO26_11") (pintype "bidirectional"))
    )
    (net (code "70") (name "unconnected-(MD1-IO27-Pad12)") (class "Default")
      (node (ref "MD1") (pin "12") (pinfunction "IO27_12") (pintype "bidirectional"))
    )
    (net (code "71") (name "unconnected-(MD1-IO32-Pad8)") (class "Default")
      (node (ref "MD1") (pin "8") (pinfunction "IO32_8") (pintype "bidirectional"))
    )
    (net (code "72") (name "unconnected-(MD1-IO33-Pad9)") (class "Default")
      (node (ref "MD1") (pin "9") (pinfunction "IO33_9") (pintype "bidirectional"))
    )
    (net (code "73") (name "unconnected-(MD1-IO34-Pad6)") (class "Default")
      (node (ref "MD1") (pin "6") (pinfunction "IO34_6") (pintype "bidirectional"))
    )
    (net (code "74") (name "unconnected-(MD1-IO35-Pad7)") (class "Default")
      (node (ref "MD1") (pin "7") (pinfunction "IO35_7") (pintype "bidirectional"))
    )
    (net (code "75") (name "unconnected-(MD1-NC-Pad32)") (class "Default")
      (node (ref "MD1") (pin "32") (pinfunction "NC_32") (pintype "passive"))
    )
    (net (code "76") (name "unconnected-(MD1-SD0-Pad21)") (class "Default")
      (node (ref "MD1") (pin "21") (pinfunction "SD0_21") (pintype "bidirectional"))
    )
    (net (code "77") (name "unconnected-(MD1-SD1-Pad22)") (class "Default")
      (node (ref "MD1") (pin "22") (pinfunction "SD1_22") (pintype "bidirectional"))
    )
    (net (code "78") (name "unconnected-(MD1-SD2-Pad17)") (class "Default")
      (node (ref "MD1") (pin "17") (pinfunction "SD2_17") (pintype "bidirectional"))
    )
    (net (code "79") (name "unconnected-(MD1-SD3-Pad18)") (class "Default")
      (node (ref "MD1") (pin "18") (pinfunction "SD3_18") (pintype "bidirectional"))
    )
    (net (code "80") (name "unconnected-(MD1-SENSOR_VN-Pad5)") (class "Default")
      (node (ref "MD1") (pin "5") (pinfunction "SENSOR_VN_5") (pintype "bidirectional"))
    )
    (net (code "81") (name "unconnected-(MD1-SENSOR_VP-Pad4)") (class "Default")
      (node (ref "MD1") (pin "4") (pinfunction "SENSOR_VP_4") (pintype "bidirectional"))
    )
    (net (code "82") (name "unconnected-(U3-D-Pad4)") (class "Default")
      (node (ref "U3") (pin "4") (pinfunction "D_4") (pintype "passive"))
    )
  )
)
